# Sheet_lm12to5.net
KiCad netlist of a schematic drawn in Altium Designer
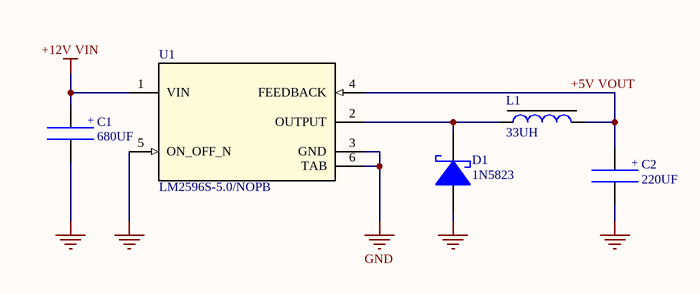
[diagram p0: Sheet_lm12to5.SchDoc]

(export (version "E")
  (design (tool "Eeschema 10.0.6"))
  (components
    (comp (ref "C1")
      (value "680UF")
      (footprint "ESY687M025AH4AA")
      (description "CAP ALUM 680UF 20% 25V RADIAL TH")
      (libsource (lib "Schlib_lm12to5") (part "ESY687M025AH4AA"))
    )
    (comp (ref "C2")
      (value "220UF")
      (footprint "35ZLJ220M8X16")
      (description "CAP ALUM 220UF 20% 35V RADIAL TH")
      (libsource (lib "Schlib_lm12to5") (part "35ZLJ220M8X16"))
    )
    (comp (ref "D1")
      (value "1N5823")
      (footprint "DIODE_1N5823_SSM")
      (description "DIODE SCHOTTKY 20V 5A AXIAL")
      (libsource (lib "Schlib_lm12to5") (part "1N5823"))
    )
    (comp (ref "L1")
      (value "33UH")
      (footprint "7447706330")
      (description "FIXED IND 33UH 3A 60 MOHM SMD")
      (libsource (lib "Schlib_lm12to5") (part "7447706330"))
    )
    (comp (ref "U1")
      (value "LM2596S-5.0/NOPB")
      (footprint "LM2596")
      (description "SIMPLE SWITCHER&reg; 4.5V to 40V, 3A Low Component Count Step-Down Regulator 5-DDPAK/TO-263")
      (fields
        (field (name "PARTNUMBER") "LM2596SX-ADJ/NOPB")
        (field (name "ALTERNATE_PARTNUMBER") "LM2596S-ADJ/NOPB")
        (field (name "COPYRIGHT") "Copyright (C) 2025 Ultra Librarian. All rights reserved.")
      )
      (libsource (lib "Schlib_lm12to5") (part "LM2596S-5.0NOPB"))
    )
  )
  (nets
    (net (code "1") (name "+12V VIN") (class "Default")
      (node (ref "C1") (pin "1") (pinfunction "+_1") (pintype "passive"))
      (node (ref "U1") (pin "1") (pinfunction "VIN_1") (pintype "power_in"))
    )
    (net (code "2") (name "/+5V VOUT") (class "Default")
      (node (ref "C2") (pin "1") (pinfunction "+_1") (pintype "passive"))
      (node (ref "L1") (pin "2") (pinfunction "2_2") (pintype "passive"))
      (node (ref "U1") (pin "4") (pinfunction "FEEDBACK_4") (pintype "input"))
    )
    (net (code "3") (name "GND") (class "Default")
      (node (ref "C1") (pin "2") (pinfunction "2_2") (pintype "passive"))
      (node (ref "C2") (pin "2") (pinfunction "2_2") (pintype "passive"))
      (node (ref "D1") (pin "2") (pinfunction "K_2") (pintype "passive"))
      (node (ref "U1") (pin "3") (pinfunction "GND_3") (pintype "power_in"))
      (node (ref "U1") (pin "5") (pinfunction "ON_OFF_N_5") (pintype "input"))
      (node (ref "U1") (pin "6") (pinfunction "TAB_6") (pintype "power_in"))
    )
    (net (code "4") (name "Net-(D1-A)") (class "Default")
      (node (ref "D1") (pin "1") (pinfunction "A_1") (pintype "passive"))
      (node (ref "L1") (pin "1") (pinfunction "1_1") (pintype "passive"))
      (node (ref "U1") (pin "2") (pinfunction "OUTPUT_2") (pintype "power_in"))
    )
  )
)
